# CatToy2.net
KiCad netlist of a schematic drawn in Altium Designer
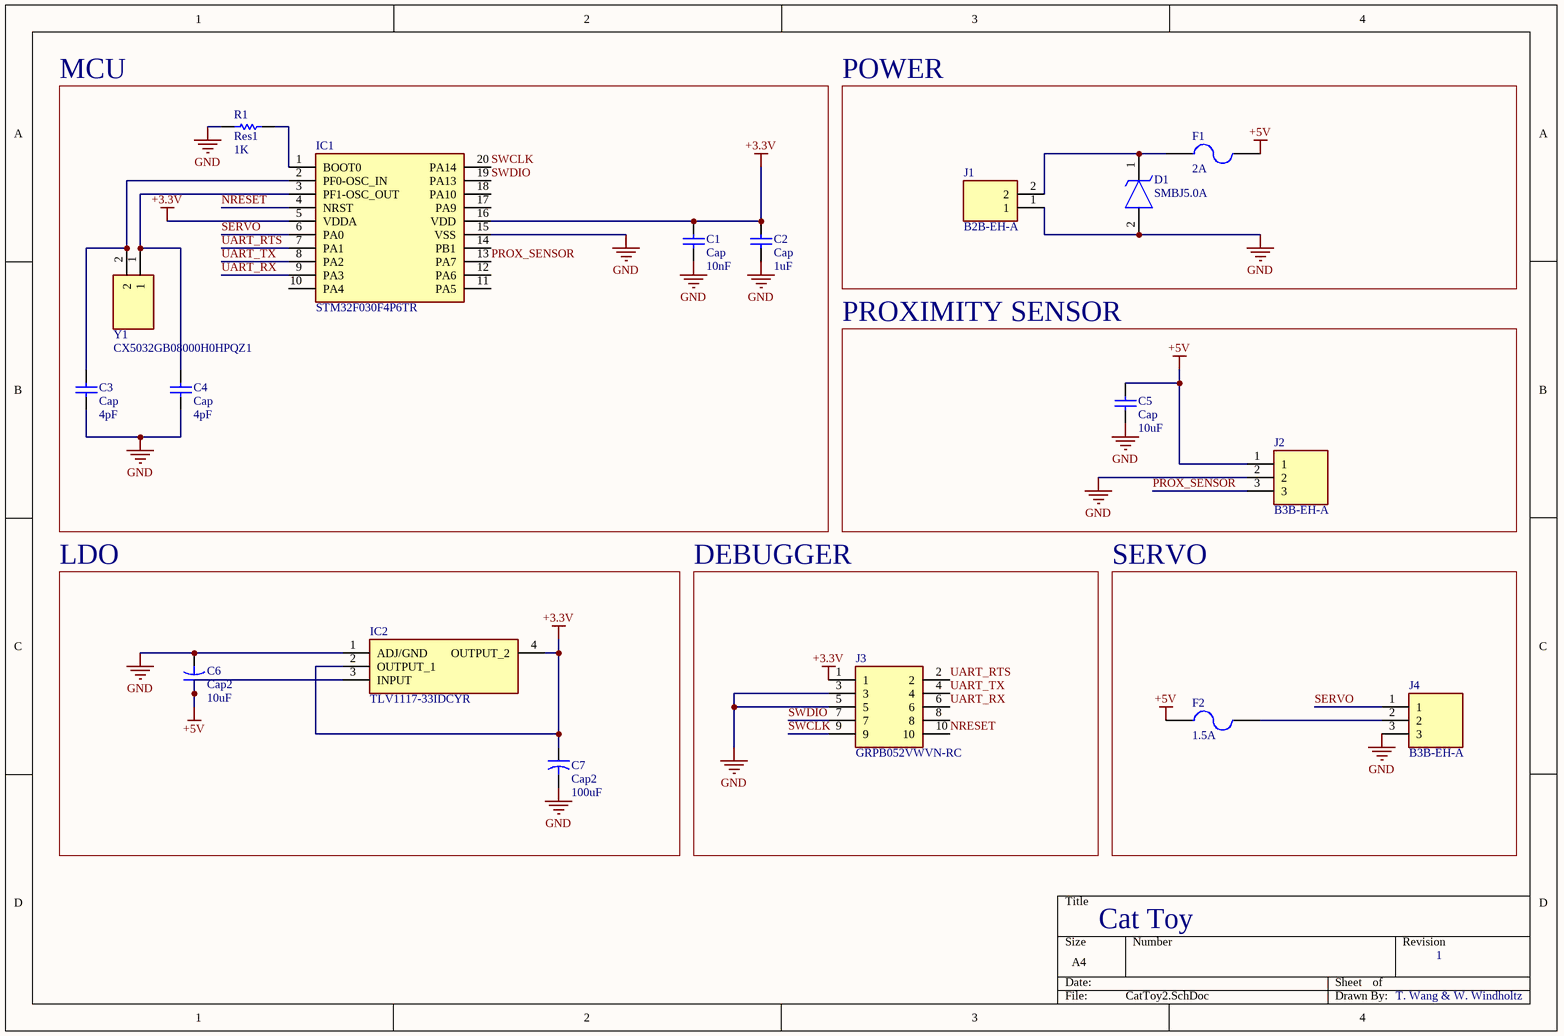
[diagram p0: CatToy2.SchDoc]

(export (version "E")
  (design (tool "Eeschema 10.0.6"))
  (components
    (comp (ref "C1")
      (value "Cap")
      (footprint "C0805")
      (description "Capacitor")
      (fields (field (name "ALTIUM_VALUE") "10nF") (field (name "PUBLISHER") "Altium Limited"))
      (libsource (lib "Miscellaneous Devices") (part "Cap"))
    )
    (comp (ref "C2")
      (value "Cap")
      (footprint "C0805")
      (description "Capacitor")
      (fields (field (name "ALTIUM_VALUE") "1uF") (field (name "PUBLISHER") "Altium Limited"))
      (libsource (lib "Miscellaneous Devices") (part "Cap"))
    )
    (comp (ref "C3")
      (value "Cap")
      (footprint "C0805")
      (description "Capacitor")
      (fields (field (name "ALTIUM_VALUE") "4pF") (field (name "PUBLISHER") "Altium Limited"))
      (libsource (lib "Miscellaneous Devices") (part "Cap"))
    )
    (comp (ref "C4")
      (value "Cap")
      (footprint "C0805")
      (description "Capacitor")
      (fields (field (name "ALTIUM_VALUE") "4pF") (field (name "PUBLISHER") "Altium Limited"))
      (libsource (lib "Miscellaneous Devices") (part "Cap"))
    )
    (comp (ref "C5")
      (value "Cap")
      (footprint "C0805")
      (description "Capacitor")
      (fields (field (name "ALTIUM_VALUE") "10uF") (field (name "PUBLISHER") "Altium Limited"))
      (libsource (lib "Miscellaneous Devices") (part "Cap"))
    )
    (comp (ref "C6")
      (value "Cap2")
      (footprint "C0805")
      (description "Capacitor")
      (fields (field (name "ALTIUM_VALUE") "10uF") (field (name "PUBLISHER") "Altium Limited"))
      (libsource (lib "Miscellaneous Devices") (part "Cap2"))
    )
    (comp (ref "C7")
      (value "Cap2")
      (footprint "C0805")
      (description "Capacitor")
      (fields (field (name "ALTIUM_VALUE") "100uF") (field (name "PUBLISHER") "Altium Limited"))
      (libsource (lib "Miscellaneous Devices") (part "Cap2"))
    )
    (comp (ref "D1")
      (value "SMBJ5.0A")
      (footprint "Embedded:DIOM5436X244N")
      (description "TVS Diode (Uni-directional)")
      (libsource (lib "*") (part "SMBJ5.0A"))
    )
    (comp (ref "F1")
      (value "2A")
      (footprint "C0805")
      (description "Fuse")
      (fields (field (name "PUBLISHER") "Altium Limited"))
      (libsource (lib "Miscellaneous Devices") (part "Fuse 2"))
    )
    (comp (ref "F2")
      (value "1.5A")
      (footprint "C0805")
      (description "Fuse")
      (fields (field (name "PUBLISHER") "Altium Limited"))
      (libsource (lib "Miscellaneous Devices") (part "Fuse 2"))
    )
    (comp (ref "IC1")
      (value "STM32F030F4P6TR")
      (footprint "Embedded:SOP65P640X120-20N")
      (description "Integrated Circuit")
      (fields (field (name "MOUSER PART NUMBER") "511-STM32F030F4P6TR"))
      (libsource (lib "Embedded") (part "STM32F030F4P6TR"))
    )
    (comp (ref "IC2")
      (value "TLV1117-33IDCYR")
      (footprint "Embedded:SOT230P700X180-4N")
      (description "Integrated Circuit")
      (fields
        (field (name "MANUFACTURER_PART_NUMBER") "TLV1117-33CDCYR")
        (field (name "MOUSER PART NUMBER") "595-TLV1117-33CDCYR")
      )
      (libsource (lib "*") (part "TLV1117-33CDCYR"))
    )
    (comp (ref "J1")
      (value "B2B-EH-A")
      (footprint "Embedded:SHDR2W64P0X250_1X2_750X380X600P")
      (description "Connector")
      (libsource (lib "*") (part "B2B-EH-A"))
    )
    (comp (ref "J2")
      (value "B3B-EH-A")
      (footprint "Embedded:SHDR3W64P0X250_1X3_1000X380X600P")
      (description "Connector")
      (libsource (lib "Embedded") (part "B3B-EH-A"))
    )
    (comp (ref "J3")
      (value "GRPB052VWVN-RC")
      (footprint "Embedded:HDRV10W50P127_2X5_635X340X430P")
      (description "Connector")
      (libsource (lib "Embedded") (part "GRPB052VWVN-RC"))
    )
    (comp (ref "J4")
      (value "B3B-EH-A")
      (footprint "Embedded:SHDR3W64P0X250_1X3_1000X380X600P")
      (description "Connector")
      (libsource (lib "Embedded") (part "B3B-EH-A"))
    )
    (comp (ref "R1")
      (value "Res1")
      (footprint "C0805")
      (description "Resistor")
      (fields (field (name "ALTIUM_VALUE") "1K") (field (name "PUBLISHER") "Altium Limited"))
      (libsource (lib "Miscellaneous Devices") (part "Res1"))
    )
    (comp (ref "Y1")
      (value "CX5032GB08000H0HPQZ1")
      (footprint "Embedded:CX5032GB08000H0HPQZ1")
      (description "Crystal or Oscillator")
      (fields (field (name "MOUSER PART NUMBER") "581-CX532GB8HHPQZ1"))
      (libsource (lib "*") (part "CX5032GB08000H0HPQZ1"))
    )
  )
  (nets
    (net (code "1") (name "+3.3V") (class "Default")
      (node (ref "C1") (pin "2") (pinfunction "2_2") (pintype "passive"))
      (node (ref "C2") (pin "2") (pinfunction "2_2") (pintype "passive"))
      (node (ref "C7") (pin "1") (pinfunction "1_1") (pintype "passive"))
      (node (ref "IC1") (pin "16") (pinfunction "VDD_16") (pintype "passive"))
      (node (ref "IC1") (pin "5") (pinfunction "VDDA_5") (pintype "passive"))
      (node (ref "IC2") (pin "2") (pinfunction "OUTPUT_1_2") (pintype "passive"))
      (node (ref "IC2") (pin "4") (pinfunction "OUTPUT_2_4") (pintype "passive"))
      (node (ref "J3") (pin "1") (pinfunction "1_1") (pintype "passive"))
    )
    (net (code "2") (name "+5V") (class "Default")
      (node (ref "C5") (pin "2") (pinfunction "2_2") (pintype "passive"))
      (node (ref "C6") (pin "1") (pinfunction "1_1") (pintype "passive"))
      (node (ref "F1") (pin "2") (pinfunction "2_2") (pintype "passive"))
      (node (ref "F2") (pin "1") (pinfunction "1_1") (pintype "passive"))
      (node (ref "IC2") (pin "3") (pinfunction "INPUT_3") (pintype "passive"))
      (node (ref "J2") (pin "1") (pinfunction "1_1") (pintype "passive"))
    )
    (net (code "3") (name "/NRESET") (class "Default")
      (node (ref "IC1") (pin "4") (pinfunction "NRST_4") (pintype "passive"))
      (node (ref "J3") (pin "10") (pinfunction "10_10") (pintype "passive"))
    )
    (net (code "4") (name "/PROX_SENSOR") (class "Default")
      (node (ref "IC1") (pin "13") (pinfunction "PA7_13") (pintype "passive"))
      (node (ref "J2") (pin "3") (pinfunction "3_3") (pintype "passive"))
    )
    (net (code "5") (name "/SERVO") (class "Default")
      (node (ref "IC1") (pin "6") (pinfunction "PA0_6") (pintype "passive"))
      (node (ref "J4") (pin "1") (pinfunction "1_1") (pintype "passive"))
    )
    (net (code "6") (name "/SWCLK") (class "Default")
      (node (ref "IC1") (pin "20") (pinfunction "PA14_20") (pintype "passive"))
      (node (ref "J3") (pin "9") (pinfunction "9_9") (pintype "passive"))
    )
    (net (code "7") (name "/SWDIO") (class "Default")
      (node (ref "IC1") (pin "19") (pinfunction "PA13_19") (pintype "passive"))
      (node (ref "J3") (pin "7") (pinfunction "7_7") (pintype "passive"))
    )
    (net (code "8") (name "/UART_RTS") (class "Default")
      (node (ref "IC1") (pin "7") (pinfunction "PA1_7") (pintype "passive"))
      (node (ref "J3") (pin "2") (pinfunction "2_2") (pintype "passive"))
    )
    (net (code "9") (name "/UART_RX") (class "Default")
      (node (ref "IC1") (pin "9") (pinfunction "PA3_9") (pintype "passive"))
      (node (ref "J3") (pin "6") (pinfunction "6_6") (pintype "passive"))
    )
    (net (code "10") (name "/UART_TX") (class "Default")
      (node (ref "IC1") (pin "8") (pinfunction "PA2_8") (pintype "passive"))
      (node (ref "J3") (pin "4") (pinfunction "4_4") (pintype "passive"))
    )
    (net (code "11") (name "GND") (class "Default")
      (node (ref "C1") (pin "1") (pinfunction "1_1") (pintype "passive"))
      (node (ref "C2") (pin "1") (pinfunction "1_1") (pintype "passive"))
      (node (ref "C3") (pin "1") (pinfunction "1_1") (pintype "passive"))
      (node (ref "C4") (pin "1") (pinfunction "1_1") (pintype "passive"))
      (node (ref "C5") (pin "1") (pinfunction "1_1") (pintype "passive"))
      (node (ref "C6") (pin "2") (pinfunction "2_2") (pintype "passive"))
      (node (ref "C7") (pin "2") (pinfunction "2_2") (pintype "passive"))
      (node (ref "D1") (pin "2") (pinfunction "A_2") (pintype "passive"))
      (node (ref "IC1") (pin "15") (pinfunction "VSS_15") (pintype "passive"))
      (node (ref "IC2") (pin "1") (pinfunction "ADJ/GND_1") (pintype "passive"))
      (node (ref "J1") (pin "1") (pinfunction "1_1") (pintype "passive"))
      (node (ref "J2") (pin "2") (pinfunction "2_2") (pintype "passive"))
      (node (ref "J3") (pin "3") (pinfunction "3_3") (pintype "passive"))
      (node (ref "J3") (pin "5") (pinfunction "5_5") (pintype "passive"))
      (node (ref "J4") (pin "3") (pinfunction "3_3") (pintype "passive"))
      (node (ref "R1") (pin "1") (pinfunction "1_1") (pintype "passive"))
    )
    (net (code "12") (name "Net-(D1-K)") (class "Default")
      (node (ref "D1") (pin "1") (pinfunction "K_1") (pintype "passive"))
      (node (ref "F1") (pin "1") (pinfunction "1_1") (pintype "passive"))
      (node (ref "J1") (pin "2") (pinfunction "2_2") (pintype "passive"))
    )
    (net (code "13") (name "Net-(F2-Pad2)") (class "Default")
      (node (ref "F2") (pin "2") (pinfunction "2_2") (pintype "passive"))
      (node (ref "J4") (pin "2") (pinfunction "2_2") (pintype "passive"))
    )
    (net (code "14") (name "Net-(IC1-BOOT0)") (class "Default")
      (node (ref "IC1") (pin "1") (pinfunction "BOOT0_1") (pintype "passive"))
      (node (ref "R1") (pin "2") (pinfunction "2_2") (pintype "passive"))
    )
    (net (code "15") (name "Net-(IC1-PF0-OSC_IN)") (class "Default")
      (node (ref "C3") (pin "2") (pinfunction "2_2") (pintype "passive"))
      (node (ref "IC1") (pin "2") (pinfunction "PF0-OSC_IN_2") (pintype "passive"))
      (node (ref "Y1") (pin "2") (pinfunction "2_2") (pintype "passive"))
    )
    (net (code "16") (name "Net-(IC1-PF1-OSC_OUT)") (class "Default")
      (node (ref "C4") (pin "2") (pinfunction "2_2") (pintype "passive"))
      (node (ref "IC1") (pin "3") (pinfunction "PF1-OSC_OUT_3") (pintype "passive"))
      (node (ref "Y1") (pin "1") (pinfunction "1_1") (pintype "passive"))
    )
    (net (code "17") (name "unconnected-(IC1-PA4-Pad10)") (class "Default")
      (node (ref "IC1") (pin "10") (pinfunction "PA4_10") (pintype "passive"))
    )
    (net (code "18") (name "unconnected-(IC1-PA5-Pad11)") (class "Default")
      (node (ref "IC1") (pin "11") (pinfunction "PA5_11") (pintype "passive"))
    )
    (net (code "19") (name "unconnected-(IC1-PA6-Pad12)") (class "Default")
      (node (ref "IC1") (pin "12") (pinfunction "PA6_12") (pintype "passive"))
    )
    (net (code "20") (name "unconnected-(IC1-PA9-Pad17)") (class "Default")
      (node (ref "IC1") (pin "17") (pinfunction "PA9_17") (pintype "passive"))
    )
    (net (code "21") (name "unconnected-(IC1-PA10-Pad18)") (class "Default")
      (node (ref "IC1") (pin "18") (pinfunction "PA10_18") (pintype "passive"))
    )
    (net (code "22") (name "unconnected-(IC1-PB1-Pad14)") (class "Default")
      (node (ref "IC1") (pin "14") (pinfunction "PB1_14") (pintype "passive"))
    )
    (net (code "23") (name "unconnected-(J3-Pad8)") (class "Default")
      (node (ref "J3") (pin "8") (pinfunction "8_8") (pintype "passive"))
    )
  )
)
